# TinyBattery_I2C_V2.net
KiCad netlist of a schematic drawn in EAGLE
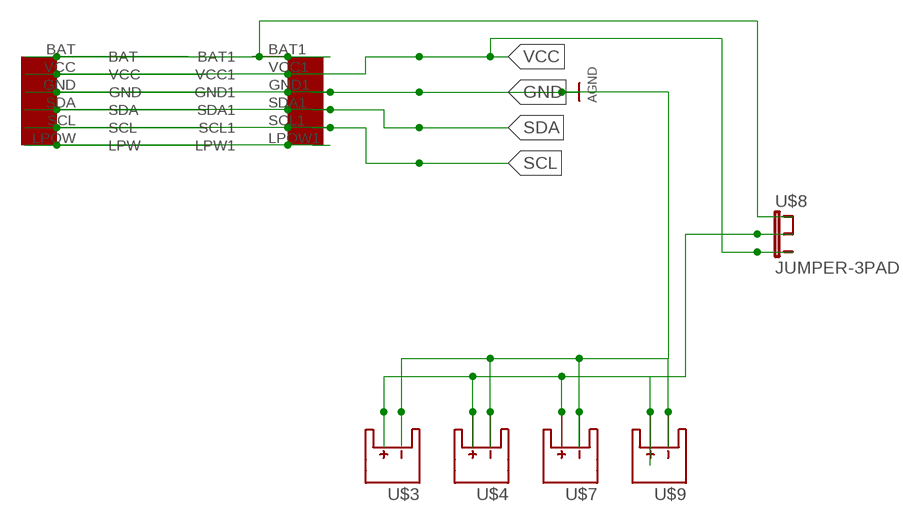
[diagram p0: schematic, sheet 1]

(export (version "E")
  (design (tool "Eeschema 10.0.6"))
  (components
    (comp (ref "U$1")
      (value "EZ-I2CHEADERV1")
      (footprint "eagle-import:EZ-I2CHEADERV1")
      (libsource (lib "eagle-import") (part "EZ-I2CHEADERV1"))
    )
    (comp (ref "U$3")
      (value "BATTERY_1.25MM_PINHOLES")
      (footprint "eagle-import:BATTERY_1.25MM_PINHOLES")
      (libsource (lib "eagle-import") (part "BATTERY_1.25MM_PINHOLES"))
    )
    (comp (ref "U$4")
      (value "BATTERY_1.25MM_PINHOLES")
      (footprint "eagle-import:BATTERY_1.25MM_PINHOLES")
      (libsource (lib "eagle-import") (part "BATTERY_1.25MM_PINHOLES"))
    )
    (comp (ref "U$7")
      (value "BATTERY_1.25MM_PINHOLES")
      (footprint "eagle-import:BATTERY_1.25MM_PINHOLES")
      (libsource (lib "eagle-import") (part "BATTERY_1.25MM_PINHOLES"))
    )
    (comp (ref "U$8")
      (value "JUMPER-3PAD")
      (footprint "eagle-import:JUMPER-3PAD")
      (libsource (lib "eagle-import") (part "JUMPER-3PAD"))
    )
    (comp (ref "U$9")
      (value "BATTERY_1.25MM_PINHOLES")
      (footprint "eagle-import:BATTERY_1.25MM_PINHOLES")
      (libsource (lib "eagle-import") (part "BATTERY_1.25MM_PINHOLES"))
    )
  )
  (nets
    (net (code "1") (name "GND") (class "Default")
      (node (ref "U$1") (pin "GND") (pinfunction "GND_GND") (pintype "bidirectional"))
      (node (ref "U$1") (pin "GND1") (pinfunction "GND1_GND1") (pintype "bidirectional"))
      (node (ref "U$3") (pin "-") (pinfunction "-_-") (pintype "bidirectional"))
      (node (ref "U$4") (pin "-") (pinfunction "-_-") (pintype "bidirectional"))
      (node (ref "U$7") (pin "-") (pinfunction "-_-") (pintype "bidirectional"))
      (node (ref "U$9") (pin "-") (pinfunction "-_-") (pintype "bidirectional"))
    )
    (net (code "2") (name "Net-(U$1-LPW)") (class "Default")
      (node (ref "U$1") (pin "LPOW") (pinfunction "LPW_LPOW") (pintype "bidirectional"))
      (node (ref "U$1") (pin "LPOW1") (pinfunction "LPW1_LPOW1") (pintype "bidirectional"))
    )
    (net (code "3") (name "Net-(U$1-PadBAT)") (class "Default")
      (node (ref "U$1") (pin "BAT") (pinfunction "BAT_BAT") (pintype "bidirectional"))
      (node (ref "U$1") (pin "BAT1") (pinfunction "BAT1_BAT1") (pintype "bidirectional"))
      (node (ref "U$8") (pin "1") (pinfunction "1_1") (pintype "passive"))
    )
    (net (code "4") (name "Net-(U$3-Pad+)") (class "Default")
      (node (ref "U$3") (pin "+") (pinfunction "+_+") (pintype "bidirectional"))
      (node (ref "U$4") (pin "+") (pinfunction "+_+") (pintype "bidirectional"))
      (node (ref "U$7") (pin "+") (pinfunction "+_+") (pintype "bidirectional"))
      (node (ref "U$8") (pin "2") (pinfunction "2_2") (pintype "passive"))
      (node (ref "U$9") (pin "+") (pinfunction "+_+") (pintype "bidirectional"))
    )
    (net (code "5") (name "SCL") (class "Default")
      (node (ref "U$1") (pin "SCL") (pinfunction "SCL_SCL") (pintype "bidirectional"))
      (node (ref "U$1") (pin "SCL1") (pinfunction "SCL1_SCL1") (pintype "bidirectional"))
    )
    (net (code "6") (name "SDA") (class "Default")
      (node (ref "U$1") (pin "SDA") (pinfunction "SDA_SDA") (pintype "bidirectional"))
      (node (ref "U$1") (pin "SDA1") (pinfunction "SDA1_SDA1") (pintype "bidirectional"))
    )
    (net (code "7") (name "VCC") (class "Default")
      (node (ref "U$1") (pin "VCC") (pinfunction "VCC_VCC") (pintype "bidirectional"))
      (node (ref "U$1") (pin "VCC1") (pinfunction "VCC1_VCC1") (pintype "bidirectional"))
      (node (ref "U$8") (pin "3") (pinfunction "3_3") (pintype "passive"))
    )
  )
)
